# CONNECTEUR_3.net
KiCad netlist of a schematic drawn in Altium Designer
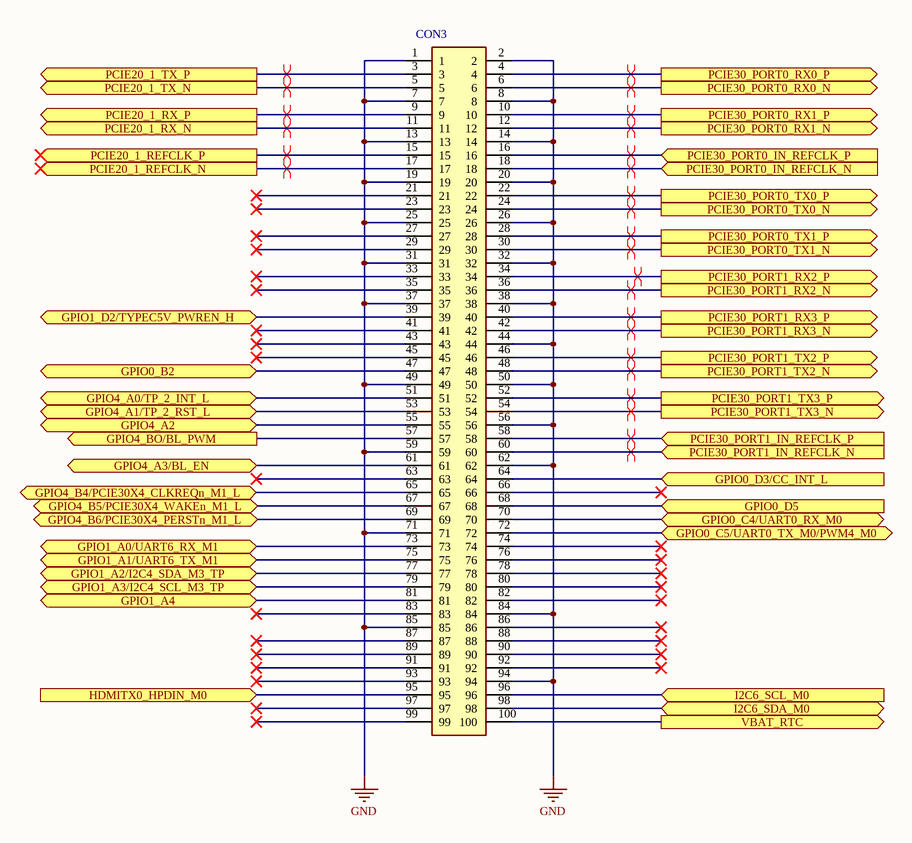
[diagram p0: CONNECTEUR_3.SchDoc]

(export (version "E")
  (design (tool "Eeschema 10.0.6"))
  (components
    (comp (ref "CON3")
      (value "DF40HC")
      (footprint "DF40HC30100DS04V51_MOD")
      (description "Stacking Board Connector, DF40 Series, Receptacle, 0.4 mm, 100, Surface Mount, G")
      (fields
        (field (name "MOUSER PART NUMBER") "798-DF40HC30100DS451")
        (field (name "ARROW PART NUMBER") "DF40HC(3.0)-100DS-0.4V(51")
      )
      (libsource (lib "DARKYDEN") (part "DF40HC(3.0)-100DS-0.4V(51)"))
    )
  )
  (nets
    (net (code "1") (name "/GPIO0_B2") (class "Default")
      (node (ref "CON3") (pin "47") (pinfunction "47_47") (pintype "passive"))
    )
    (net (code "2") (name "/GPIO0_C4{slash}UART0_RX_M0") (class "Default")
      (node (ref "CON3") (pin "70") (pinfunction "70_70") (pintype "passive"))
    )
    (net (code "3") (name "/GPIO0_C5{slash}UART0_TX_M0{slash}PWM4_M0") (class "Default")
      (node (ref "CON3") (pin "72") (pinfunction "72_72") (pintype "passive"))
    )
    (net (code "4") (name "/GPIO0_D3{slash}CC_INT_L") (class "Default")
      (node (ref "CON3") (pin "64") (pinfunction "64_64") (pintype "passive"))
    )
    (net (code "5") (name "/GPIO0_D5") (class "Default")
      (node (ref "CON3") (pin "68") (pinfunction "68_68") (pintype "passive"))
    )
    (net (code "6") (name "/GPIO1_A0{slash}UART6_RX_M1") (class "Default")
      (node (ref "CON3") (pin "73") (pinfunction "73_73") (pintype "passive"))
    )
    (net (code "7") (name "/GPIO1_A1{slash}UART6_TX_M1") (class "Default")
      (node (ref "CON3") (pin "75") (pinfunction "75_75") (pintype "passive"))
    )
    (net (code "8") (name "/GPIO1_A2{slash}I2C4_SDA_M3_TP") (class "Default")
      (node (ref "CON3") (pin "77") (pinfunction "77_77") (pintype "passive"))
    )
    (net (code "9") (name "/GPIO1_A3{slash}I2C4_SCL_M3_TP") (class "Default")
      (node (ref "CON3") (pin "79") (pinfunction "79_79") (pintype "passive"))
    )
    (net (code "10") (name "/GPIO1_A4") (class "Default")
      (node (ref "CON3") (pin "81") (pinfunction "81_81") (pintype "passive"))
    )
    (net (code "11") (name "/GPIO1_D2{slash}TYPEC5V_PWREN_H") (class "Default")
      (node (ref "CON3") (pin "39") (pinfunction "39_39") (pintype "passive"))
    )
    (net (code "12") (name "/GPIO4_A0{slash}TP_2_INT_L") (class "Default")
      (node (ref "CON3") (pin "51") (pinfunction "51_51") (pintype "passive"))
    )
    (net (code "13") (name "/GPIO4_A1{slash}TP_2_RST_L") (class "Default")
      (node (ref "CON3") (pin "53") (pinfunction "53_53") (pintype "passive"))
    )
    (net (code "14") (name "/GPIO4_A2") (class "Default")
      (node (ref "CON3") (pin "55") (pinfunction "55_55") (pintype "passive"))
    )
    (net (code "15") (name "/GPIO4_A3{slash}BL_EN") (class "Default")
      (node (ref "CON3") (pin "61") (pinfunction "61_61") (pintype "passive"))
    )
    (net (code "16") (name "/GPIO4_B4{slash}PCIE30X4_CLKREQn_M1_L") (class "Default")
      (node (ref "CON3") (pin "65") (pinfunction "65_65") (pintype "passive"))
    )
    (net (code "17") (name "/GPIO4_B5{slash}PCIE30X4_WAKEn_M1_L") (class "Default")
      (node (ref "CON3") (pin "67") (pinfunction "67_67") (pintype "passive"))
    )
    (net (code "18") (name "/GPIO4_B6{slash}PCIE30X4_PERSTn_M1_L") (class "Default")
      (node (ref "CON3") (pin "69") (pinfunction "69_69") (pintype "passive"))
    )
    (net (code "19") (name "/GPIO4_BO{slash}BL_PWM") (class "Default")
      (node (ref "CON3") (pin "57") (pinfunction "57_57") (pintype "passive"))
    )
    (net (code "20") (name "/HDMITX0_HPDIN_M0") (class "Default")
      (node (ref "CON3") (pin "95") (pinfunction "95_95") (pintype "passive"))
    )
    (net (code "21") (name "/I2C6_SCL_M0") (class "Default")
      (node (ref "CON3") (pin "96") (pinfunction "96_96") (pintype "passive"))
    )
    (net (code "22") (name "/I2C6_SDA_M0") (class "Default")
      (node (ref "CON3") (pin "98") (pinfunction "98_98") (pintype "passive"))
    )
    (net (code "23") (name "/PCIE20_1_REFCLK_N") (class "Default")
      (node (ref "CON3") (pin "17") (pinfunction "17_17") (pintype "passive"))
    )
    (net (code "24") (name "/PCIE20_1_REFCLK_P") (class "Default")
      (node (ref "CON3") (pin "15") (pinfunction "15_15") (pintype "passive"))
    )
    (net (code "25") (name "/PCIE20_1_RX_N") (class "Default")
      (node (ref "CON3") (pin "11") (pinfunction "11_11") (pintype "passive"))
    )
    (net (code "26") (name "/PCIE20_1_RX_P") (class "Default")
      (node (ref "CON3") (pin "9") (pinfunction "9_9") (pintype "passive"))
    )
    (net (code "27") (name "/PCIE20_1_TX_N") (class "Default")
      (node (ref "CON3") (pin "5") (pinfunction "5_5") (pintype "passive"))
    )
    (net (code "28") (name "/PCIE20_1_TX_P") (class "Default")
      (node (ref "CON3") (pin "3") (pinfunction "3_3") (pintype "passive"))
    )
    (net (code "29") (name "/PCIE30_PORT0_IN_REFCLK_N") (class "Default")
      (node (ref "CON3") (pin "18") (pinfunction "18_18") (pintype "passive"))
    )
    (net (code "30") (name "/PCIE30_PORT0_IN_REFCLK_P") (class "Default")
      (node (ref "CON3") (pin "16") (pinfunction "16_16") (pintype "passive"))
    )
    (net (code "31") (name "/PCIE30_PORT0_RX0_N") (class "Default")
      (node (ref "CON3") (pin "6") (pinfunction "6_6") (pintype "passive"))
    )
    (net (code "32") (name "/PCIE30_PORT0_RX0_P") (class "Default")
      (node (ref "CON3") (pin "4") (pinfunction "4_4") (pintype "passive"))
    )
    (net (code "33") (name "/PCIE30_PORT0_RX1_N") (class "Default")
      (node (ref "CON3") (pin "12") (pinfunction "12_12") (pintype "passive"))
    )
    (net (code "34") (name "/PCIE30_PORT0_RX1_P") (class "Default")
      (node (ref "CON3") (pin "10") (pinfunction "10_10") (pintype "passive"))
    )
    (net (code "35") (name "/PCIE30_PORT0_TX0_N") (class "Default")
      (node (ref "CON3") (pin "24") (pinfunction "24_24") (pintype "passive"))
    )
    (net (code "36") (name "/PCIE30_PORT0_TX0_P") (class "Default")
      (node (ref "CON3") (pin "22") (pinfunction "22_22") (pintype "passive"))
    )
    (net (code "37") (name "/PCIE30_PORT0_TX1_N") (class "Default")
      (node (ref "CON3") (pin "30") (pinfunction "30_30") (pintype "passive"))
    )
    (net (code "38") (name "/PCIE30_PORT0_TX1_P") (class "Default")
      (node (ref "CON3") (pin "28") (pinfunction "28_28") (pintype "passive"))
    )
    (net (code "39") (name "/PCIE30_PORT1_IN_REFCLK_N") (class "Default")
      (node (ref "CON3") (pin "60") (pinfunction "60_60") (pintype "passive"))
    )
    (net (code "40") (name "/PCIE30_PORT1_IN_REFCLK_P") (class "Default")
      (node (ref "CON3") (pin "58") (pinfunction "58_58") (pintype "passive"))
    )
    (net (code "41") (name "/PCIE30_PORT1_RX2_N") (class "Default")
      (node (ref "CON3") (pin "36") (pinfunction "36_36") (pintype "passive"))
    )
    (net (code "42") (name "/PCIE30_PORT1_RX2_P") (class "Default")
      (node (ref "CON3") (pin "34") (pinfunction "34_34") (pintype "passive"))
    )
    (net (code "43") (name "/PCIE30_PORT1_RX3_N") (class "Default")
      (node (ref "CON3") (pin "42") (pinfunction "42_42") (pintype "passive"))
    )
    (net (code "44") (name "/PCIE30_PORT1_RX3_P") (class "Default")
      (node (ref "CON3") (pin "40") (pinfunction "40_40") (pintype "passive"))
    )
    (net (code "45") (name "/PCIE30_PORT1_TX2_N") (class "Default")
      (node (ref "CON3") (pin "48") (pinfunction "48_48") (pintype "passive"))
    )
    (net (code "46") (name "/PCIE30_PORT1_TX2_P") (class "Default")
      (node (ref "CON3") (pin "46") (pinfunction "46_46") (pintype "passive"))
    )
    (net (code "47") (name "/PCIE30_PORT1_TX3_N") (class "Default")
      (node (ref "CON3") (pin "54") (pinfunction "54_54") (pintype "passive"))
    )
    (net (code "48") (name "/PCIE30_PORT1_TX3_P") (class "Default")
      (node (ref "CON3") (pin "52") (pinfunction "52_52") (pintype "passive"))
    )
    (net (code "49") (name "/VBAT_RTC") (class "Default")
      (node (ref "CON3") (pin "100") (pinfunction "100_100") (pintype "passive"))
    )
    (net (code "50") (name "GND") (class "Default")
      (node (ref "CON3") (pin "1") (pinfunction "1_1") (pintype "passive"))
      (node (ref "CON3") (pin "13") (pinfunction "13_13") (pintype "passive"))
      (node (ref "CON3") (pin "14") (pinfunction "14_14") (pintype "passive"))
      (node (ref "CON3") (pin "19") (pinfunction "19_19") (pintype "passive"))
      (node (ref "CON3") (pin "2") (pinfunction "2_2") (pintype "passive"))
      (node (ref "CON3") (pin "20") (pinfunction "20_20") (pintype "passive"))
      (node (ref "CON3") (pin "25") (pinfunction "25_25") (pintype "passive"))
      (node (ref "CON3") (pin "26") (pinfunction "26_26") (pintype "passive"))
      (node (ref "CON3") (pin "31") (pinfunction "31_31") (pintype "passive"))
      (node (ref "CON3") (pin "32") (pinfunction "32_32") (pintype "passive"))
      (node (ref "CON3") (pin "37") (pinfunction "37_37") (pintype "passive"))
      (node (ref "CON3") (pin "38") (pinfunction "38_38") (pintype "passive"))
      (node (ref "CON3") (pin "44") (pinfunction "44_44") (pintype "passive"))
      (node (ref "CON3") (pin "49") (pinfunction "49_49") (pintype "passive"))
      (node (ref "CON3") (pin "50") (pinfunction "50_50") (pintype "passive"))
      (node (ref "CON3") (pin "56") (pinfunction "56_56") (pintype "passive"))
      (node (ref "CON3") (pin "59") (pinfunction "59_59") (pintype "passive"))
      (node (ref "CON3") (pin "62") (pinfunction "62_62") (pintype "passive"))
      (node (ref "CON3") (pin "7") (pinfunction "7_7") (pintype "passive"))
      (node (ref "CON3") (pin "71") (pinfunction "71_71") (pintype "passive"))
      (node (ref "CON3") (pin "8") (pinfunction "8_8") (pintype "passive"))
      (node (ref "CON3") (pin "84") (pinfunction "84_84") (pintype "passive"))
      (node (ref "CON3") (pin "85") (pinfunction "85_85") (pintype "passive"))
      (node (ref "CON3") (pin "94") (pinfunction "94_94") (pintype "passive"))
    )
    (net (code "51") (name "unconnected-(CON3-Pad21)") (class "Default")
      (node (ref "CON3") (pin "21") (pinfunction "21_21") (pintype "passive+no_connect"))
    )
    (net (code "52") (name "unconnected-(CON3-Pad23)") (class "Default")
      (node (ref "CON3") (pin "23") (pinfunction "23_23") (pintype "passive+no_connect"))
    )
    (net (code "53") (name "unconnected-(CON3-Pad27)") (class "Default")
      (node (ref "CON3") (pin "27") (pinfunction "27_27") (pintype "passive+no_connect"))
    )
    (net (code "54") (name "unconnected-(CON3-Pad29)") (class "Default")
      (node (ref "CON3") (pin "29") (pinfunction "29_29") (pintype "passive+no_connect"))
    )
    (net (code "55") (name "unconnected-(CON3-Pad33)") (class "Default")
      (node (ref "CON3") (pin "33") (pinfunction "33_33") (pintype "passive+no_connect"))
    )
    (net (code "56") (name "unconnected-(CON3-Pad35)") (class "Default")
      (node (ref "CON3") (pin "35") (pinfunction "35_35") (pintype "passive+no_connect"))
    )
    (net (code "57") (name "unconnected-(CON3-Pad41)") (class "Default")
      (node (ref "CON3") (pin "41") (pinfunction "41_41") (pintype "passive+no_connect"))
    )
    (net (code "58") (name "unconnected-(CON3-Pad43)") (class "Default")
      (node (ref "CON3") (pin "43") (pinfunction "43_43") (pintype "passive+no_connect"))
    )
    (net (code "59") (name "unconnected-(CON3-Pad45)") (class "Default")
      (node (ref "CON3") (pin "45") (pinfunction "45_45") (pintype "passive+no_connect"))
    )
    (net (code "60") (name "unconnected-(CON3-Pad63)") (class "Default")
      (node (ref "CON3") (pin "63") (pinfunction "63_63") (pintype "passive+no_connect"))
    )
    (net (code "61") (name "unconnected-(CON3-Pad66)") (class "Default")
      (node (ref "CON3") (pin "66") (pinfunction "66_66") (pintype "passive+no_connect"))
    )
    (net (code "62") (name "unconnected-(CON3-Pad74)") (class "Default")
      (node (ref "CON3") (pin "74") (pinfunction "74_74") (pintype "passive+no_connect"))
    )
    (net (code "63") (name "unconnected-(CON3-Pad76)") (class "Default")
      (node (ref "CON3") (pin "76") (pinfunction "76_76") (pintype "passive+no_connect"))
    )
    (net (code "64") (name "unconnected-(CON3-Pad78)") (class "Default")
      (node (ref "CON3") (pin "78") (pinfunction "78_78") (pintype "passive+no_connect"))
    )
    (net (code "65") (name "unconnected-(CON3-Pad80)") (class "Default")
      (node (ref "CON3") (pin "80") (pinfunction "80_80") (pintype "passive+no_connect"))
    )
    (net (code "66") (name "unconnected-(CON3-Pad82)") (class "Default")
      (node (ref "CON3") (pin "82") (pinfunction "82_82") (pintype "passive+no_connect"))
    )
    (net (code "67") (name "unconnected-(CON3-Pad83)") (class "Default")
      (node (ref "CON3") (pin "83") (pinfunction "83_83") (pintype "passive+no_connect"))
    )
    (net (code "68") (name "unconnected-(CON3-Pad86)") (class "Default")
      (node (ref "CON3") (pin "86") (pinfunction "86_86") (pintype "passive+no_connect"))
    )
    (net (code "69") (name "unconnected-(CON3-Pad87)") (class "Default")
      (node (ref "CON3") (pin "87") (pinfunction "87_87") (pintype "passive+no_connect"))
    )
    (net (code "70") (name "unconnected-(CON3-Pad88)") (class "Default")
      (node (ref "CON3") (pin "88") (pinfunction "88_88") (pintype "passive+no_connect"))
    )
    (net (code "71") (name "unconnected-(CON3-Pad89)") (class "Default")
      (node (ref "CON3") (pin "89") (pinfunction "89_89") (pintype "passive+no_connect"))
    )
    (net (code "72") (name "unconnected-(CON3-Pad90)") (class "Default")
      (node (ref "CON3") (pin "90") (pinfunction "90_90") (pintype "passive+no_connect"))
    )
    (net (code "73") (name "unconnected-(CON3-Pad91)") (class "Default")
      (node (ref "CON3") (pin "91") (pinfunction "91_91") (pintype "passive+no_connect"))
    )
    (net (code "74") (name "unconnected-(CON3-Pad92)") (class "Default")
      (node (ref "CON3") (pin "92") (pinfunction "92_92") (pintype "passive+no_connect"))
    )
    (net (code "75") (name "unconnected-(CON3-Pad93)") (class "Default")
      (node (ref "CON3") (pin "93") (pinfunction "93_93") (pintype "passive+no_connect"))
    )
    (net (code "76") (name "unconnected-(CON3-Pad97)") (class "Default")
      (node (ref "CON3") (pin "97") (pinfunction "97_97") (pintype "passive+no_connect"))
    )
    (net (code "77") (name "unconnected-(CON3-Pad99)") (class "Default")
      (node (ref "CON3") (pin "99") (pinfunction "99_99") (pintype "passive+no_connect"))
    )
  )
)
